# analog_project_schematic_2.net
KiCad netlist of a schematic drawn in Altium Designer
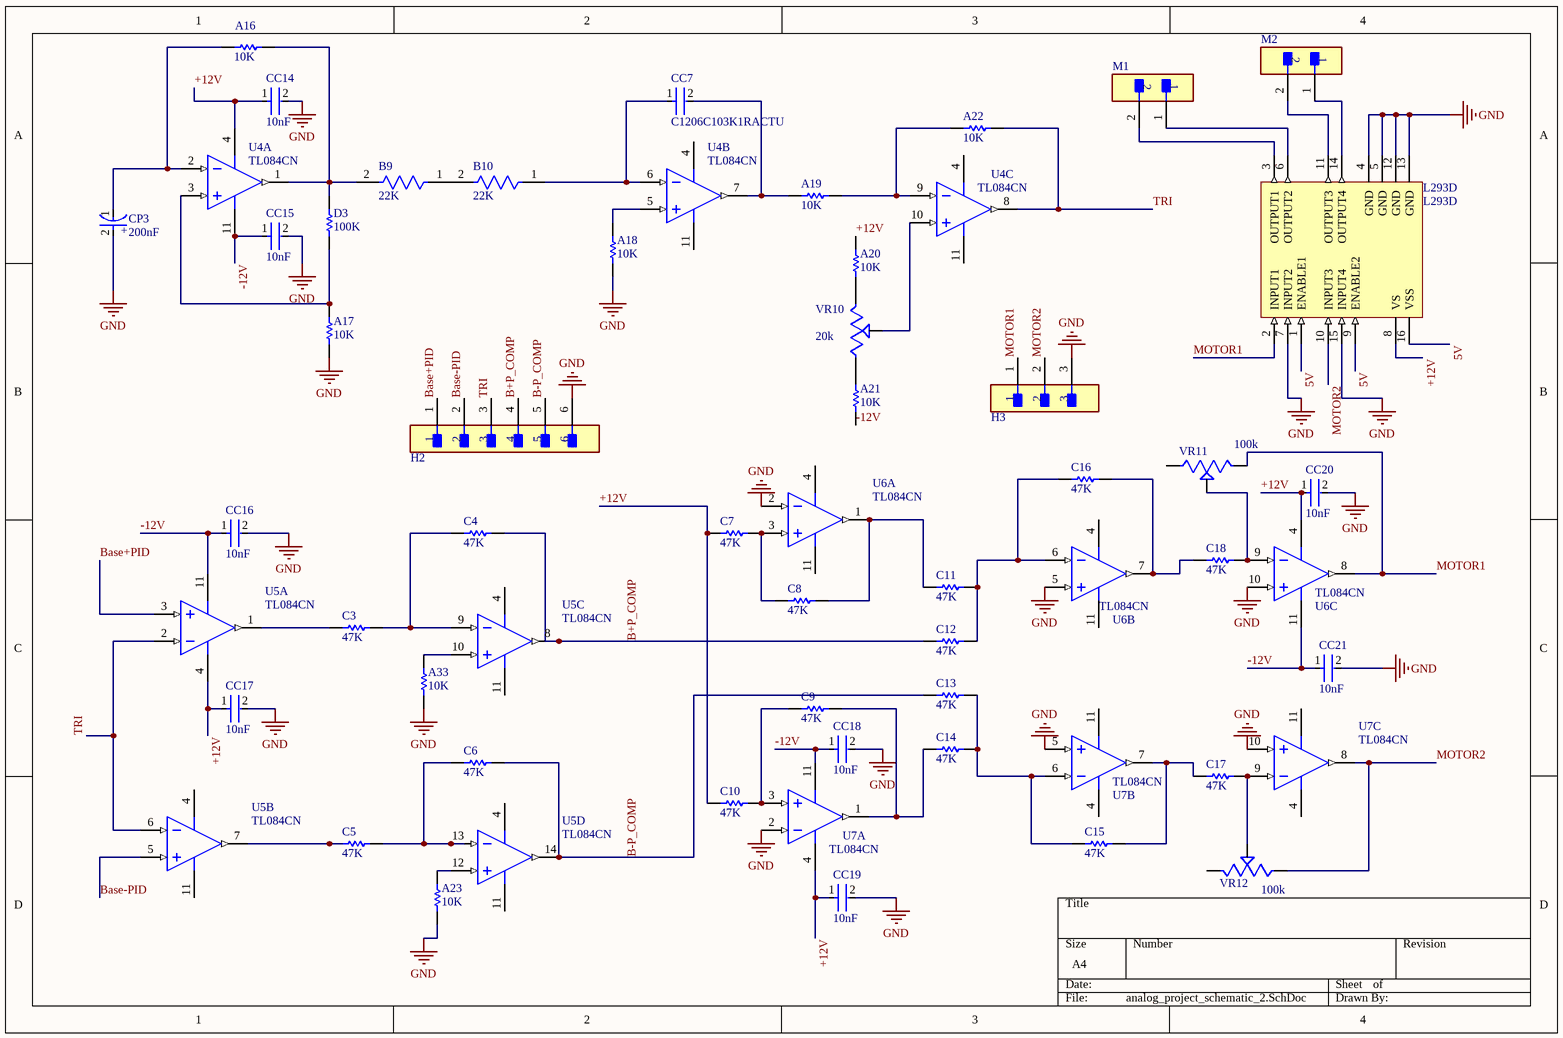
[diagram p0: analog_project_schematic_2.SchDoc]

(export (version "E")
  (design (tool "Eeschema 10.0.6"))
  (components
    (comp (ref "A16")
      (value "10K")
      (footprint "RESC3216X70X50NL05T20")
      (fields (field (name "PART NUMBER") "ERJ-8GEYJ103V") (field (name "MANUFACTURER") "Panasonic"))
      (libsource (lib "Altium Content Vault") (part "RES"))
    )
    (comp (ref "A17")
      (value "10K")
      (footprint "RESC3216X70X50NL05T20")
      (fields (field (name "PART NUMBER") "ERJ-8GEYJ103V") (field (name "MANUFACTURER") "Panasonic"))
      (libsource (lib "Altium Content Vault") (part "RES"))
    )
    (comp (ref "A18")
      (value "10K")
      (footprint "RESC3216X70X50NL05T20")
      (fields (field (name "PART NUMBER") "ERJ-8GEYJ103V") (field (name "MANUFACTURER") "Panasonic"))
      (libsource (lib "Altium Content Vault") (part "RES"))
    )
    (comp (ref "A19")
      (value "10K")
      (footprint "RESC3216X70X50NL05T20")
      (fields (field (name "PART NUMBER") "ERJ-8GEYJ103V") (field (name "MANUFACTURER") "Panasonic"))
      (libsource (lib "Altium Content Vault") (part "RES"))
    )
    (comp (ref "A20")
      (value "10K")
      (footprint "RESC3216X70X50NL05T20")
      (fields (field (name "PART NUMBER") "ERJ-8GEYJ103V") (field (name "MANUFACTURER") "Panasonic"))
      (libsource (lib "Altium Content Vault") (part "RES"))
    )
    (comp (ref "A21")
      (value "10K")
      (footprint "RESC3216X70X50NL05T20")
      (fields (field (name "PART NUMBER") "ERJ-8GEYJ103V") (field (name "MANUFACTURER") "Panasonic"))
      (libsource (lib "Altium Content Vault") (part "RES"))
    )
    (comp (ref "A22")
      (value "10K")
      (footprint "RESC3216X70X50NL05T20")
      (fields (field (name "PART NUMBER") "ERJ-8GEYJ103V") (field (name "MANUFACTURER") "Panasonic"))
      (libsource (lib "Altium Content Vault") (part "RES"))
    )
    (comp (ref "A23")
      (value "10K")
      (footprint "RESC3216X70X50NL05T20")
      (fields (field (name "PART NUMBER") "ERJ-8GEYJ103V") (field (name "MANUFACTURER") "Panasonic"))
      (libsource (lib "Altium Content Vault") (part "RES"))
    )
    (comp (ref "A33")
      (value "10K")
      (footprint "RESC3216X70X50NL05T20")
      (fields (field (name "PART NUMBER") "ERJ-8GEYJ103V") (field (name "MANUFACTURER") "Panasonic"))
      (libsource (lib "Altium Content Vault") (part "RES"))
    )
    (comp (ref "B9")
      (value "22K")
      (footprint "FP-CRCW1206-e3-IPC_A")
      (description "RES Thick Film, 22kΩ, 1%, 0.25W, 100ppm/°C, 1206")
      (fields (field (name "TOLERANCE") "1%"))
      (libsource (lib "Altium Content Vault") (part "1029c3af85768c4190bb7ad29bc67b5"))
    )
    (comp (ref "B10")
      (value "22K")
      (footprint "FP-CRCW1206-e3-IPC_A")
      (description "RES Thick Film, 22kΩ, 1%, 0.25W, 100ppm/°C, 1206")
      (fields (field (name "TOLERANCE") "1%"))
      (libsource (lib "Altium Content Vault") (part "1029c3af85768c4190bb7ad29bc67b5"))
    )
    (comp (ref "C3")
      (value "47K")
      (footprint "RESC3216X60X45LL10T20")
      (fields (field (name "PART NUMBER") "CRCW120647K0FKEA") (field (name "MANUFACTURER") "Vishay Dale"))
      (libsource (lib "Altium Content Vault") (part "RES"))
    )
    (comp (ref "C4")
      (value "47K")
      (footprint "RESC3216X60X45LL10T20")
      (fields (field (name "PART NUMBER") "CRCW120647K0FKEA") (field (name "MANUFACTURER") "Vishay Dale"))
      (libsource (lib "Altium Content Vault") (part "RES"))
    )
    (comp (ref "C5")
      (value "47K")
      (footprint "RESC3216X60X45LL10T20")
      (fields (field (name "PART NUMBER") "CRCW120647K0FKEA") (field (name "MANUFACTURER") "Vishay Dale"))
      (libsource (lib "Altium Content Vault") (part "RES"))
    )
    (comp (ref "C6")
      (value "47K")
      (footprint "RESC3216X60X45LL10T20")
      (fields (field (name "PART NUMBER") "CRCW120647K0FKEA") (field (name "MANUFACTURER") "Vishay Dale"))
      (libsource (lib "Altium Content Vault") (part "RES"))
    )
    (comp (ref "C7")
      (value "47K")
      (footprint "RESC3216X60X45LL10T20")
      (fields (field (name "PART NUMBER") "CRCW120647K0FKEA") (field (name "MANUFACTURER") "Vishay Dale"))
      (libsource (lib "Altium Content Vault") (part "RES"))
    )
    (comp (ref "C8")
      (value "47K")
      (footprint "RESC3216X60X45LL10T20")
      (fields (field (name "PART NUMBER") "CRCW120647K0FKEA") (field (name "MANUFACTURER") "Vishay Dale"))
      (libsource (lib "Altium Content Vault") (part "RES"))
    )
    (comp (ref "C9")
      (value "47K")
      (footprint "RESC3216X60X45LL10T20")
      (fields (field (name "PART NUMBER") "CRCW120647K0FKEA") (field (name "MANUFACTURER") "Vishay Dale"))
      (libsource (lib "Altium Content Vault") (part "RES"))
    )
    (comp (ref "C10")
      (value "47K")
      (footprint "RESC3216X60X45LL10T20")
      (fields (field (name "PART NUMBER") "CRCW120647K0FKEA") (field (name "MANUFACTURER") "Vishay Dale"))
      (libsource (lib "Altium Content Vault") (part "RES"))
    )
    (comp (ref "C11")
      (value "47K")
      (footprint "RESC3216X60X45LL10T20")
      (fields (field (name "PART NUMBER") "CRCW120647K0FKEA") (field (name "MANUFACTURER") "Vishay Dale"))
      (libsource (lib "Altium Content Vault") (part "RES"))
    )
    (comp (ref "C12")
      (value "47K")
      (footprint "RESC3216X60X45LL10T20")
      (fields (field (name "PART NUMBER") "CRCW120647K0FKEA") (field (name "MANUFACTURER") "Vishay Dale"))
      (libsource (lib "Altium Content Vault") (part "RES"))
    )
    (comp (ref "C13")
      (value "47K")
      (footprint "RESC3216X60X45LL10T20")
      (fields (field (name "PART NUMBER") "CRCW120647K0FKEA") (field (name "MANUFACTURER") "Vishay Dale"))
      (libsource (lib "Altium Content Vault") (part "RES"))
    )
    (comp (ref "C14")
      (value "47K")
      (footprint "RESC3216X60X45LL10T20")
      (fields (field (name "PART NUMBER") "CRCW120647K0FKEA") (field (name "MANUFACTURER") "Vishay Dale"))
      (libsource (lib "Altium Content Vault") (part "RES"))
    )
    (comp (ref "C15")
      (value "47K")
      (footprint "RESC3216X60X45LL10T20")
      (fields (field (name "PART NUMBER") "CRCW120647K0FKEA") (field (name "MANUFACTURER") "Vishay Dale"))
      (libsource (lib "Altium Content Vault") (part "RES"))
    )
    (comp (ref "C16")
      (value "47K")
      (footprint "RESC3216X60X45LL10T20")
      (fields (field (name "PART NUMBER") "CRCW120647K0FKEA") (field (name "MANUFACTURER") "Vishay Dale"))
      (libsource (lib "Altium Content Vault") (part "RES"))
    )
    (comp (ref "C17")
      (value "47K")
      (footprint "RESC3216X60X45LL10T20")
      (fields (field (name "PART NUMBER") "CRCW120647K0FKEA") (field (name "MANUFACTURER") "Vishay Dale"))
      (libsource (lib "Altium Content Vault") (part "RES"))
    )
    (comp (ref "C18")
      (value "47K")
      (footprint "RESC3216X60X45LL10T20")
      (fields (field (name "PART NUMBER") "CRCW120647K0FKEA") (field (name "MANUFACTURER") "Vishay Dale"))
      (libsource (lib "Altium Content Vault") (part "RES"))
    )
    (comp (ref "CC7")
      (value "C1206C103K1RACTU")
      (footprint "FP-C1206C-EB-MFG")
      (description "Cap Ceramic 0.01uF 100V X7R 10% SMD 1206 125°C Plastic T/R")
      (fields
        (field (name "MANUFACTURER") "KEMET")
        (field (name "OCTOPART") "https://octopart.com/c1206c103k1ractu-kemet-117927")
      )
      (libsource (lib "Altium Content Vault") (part "b4654b650e69147ec39a6b967a45e02"))
    )
    (comp (ref "CC14")
      (value "10nF")
      (footprint "FP-C1206C-EB-MFG")
      (description "Cap Ceramic 0.01uF 100V X7R 10% SMD 1206 125°C Plastic T/R")
      (fields
        (field (name "MANUFACTURER") "KEMET")
        (field (name "MANUFACTURER PART NUMBER") "C1206C103K1RACTU")
      )
      (libsource (lib "Altium Content Vault") (part "b4654b650e69147ec39a6b967a45e02"))
    )
    (comp (ref "CC15")
      (value "10nF")
      (footprint "FP-C1206C-EB-MFG")
      (description "Cap Ceramic 0.01uF 100V X7R 10% SMD 1206 125°C Plastic T/R")
      (fields
        (field (name "MANUFACTURER") "KEMET")
        (field (name "MANUFACTURER PART NUMBER") "C1206C103K1RACTU")
      )
      (libsource (lib "Altium Content Vault") (part "b4654b650e69147ec39a6b967a45e02"))
    )
    (comp (ref "CC16")
      (value "10nF")
      (footprint "FP-C1206C-EB-MFG")
      (description "Cap Ceramic 0.01uF 100V X7R 10% SMD 1206 125°C Plastic T/R")
      (fields
        (field (name "MANUFACTURER") "KEMET")
        (field (name "MANUFACTURER PART NUMBER") "C1206C103K1RACTU")
      )
      (libsource (lib "Altium Content Vault") (part "b4654b650e69147ec39a6b967a45e02"))
    )
    (comp (ref "CC17")
      (value "10nF")
      (footprint "FP-C1206C-EB-MFG")
      (description "Cap Ceramic 0.01uF 100V X7R 10% SMD 1206 125°C Plastic T/R")
      (fields
        (field (name "MANUFACTURER") "KEMET")
        (field (name "MANUFACTURER PART NUMBER") "C1206C103K1RACTU")
      )
      (libsource (lib "Altium Content Vault") (part "b4654b650e69147ec39a6b967a45e02"))
    )
    (comp (ref "CC18")
      (value "10nF")
      (footprint "FP-C1206C-EB-MFG")
      (description "Cap Ceramic 0.01uF 100V X7R 10% SMD 1206 125°C Plastic T/R")
      (fields
        (field (name "MANUFACTURER") "KEMET")
        (field (name "MANUFACTURER PART NUMBER") "C1206C103K1RACTU")
      )
      (libsource (lib "Altium Content Vault") (part "b4654b650e69147ec39a6b967a45e02"))
    )
    (comp (ref "CC19")
      (value "10nF")
      (footprint "FP-C1206C-EB-MFG")
      (description "Cap Ceramic 0.01uF 100V X7R 10% SMD 1206 125°C Plastic T/R")
      (fields
        (field (name "MANUFACTURER") "KEMET")
        (field (name "MANUFACTURER PART NUMBER") "C1206C103K1RACTU")
      )
      (libsource (lib "Altium Content Vault") (part "b4654b650e69147ec39a6b967a45e02"))
    )
    (comp (ref "CC20")
      (value "10nF")
      (footprint "FP-C1206C-EB-MFG")
      (description "Cap Ceramic 0.01uF 100V X7R 10% SMD 1206 125°C Plastic T/R")
      (fields
        (field (name "MANUFACTURER") "KEMET")
        (field (name "MANUFACTURER PART NUMBER") "C1206C103K1RACTU")
      )
      (libsource (lib "Altium Content Vault") (part "b4654b650e69147ec39a6b967a45e02"))
    )
    (comp (ref "CC21")
      (value "10nF")
      (footprint "FP-C1206C-EB-MFG")
      (description "Cap Ceramic 0.01uF 100V X7R 10% SMD 1206 125°C Plastic T/R")
      (fields
        (field (name "MANUFACTURER") "KEMET")
        (field (name "MANUFACTURER PART NUMBER") "C1206C103K1RACTU")
      )
      (libsource (lib "Altium Content Vault") (part "b4654b650e69147ec39a6b967a45e02"))
    )
    (comp (ref "CP3")
      (value "200nF")
      (footprint "FP-EEU-FR1H101B-MFG")
      (description "CAP ALUM 100UF 20% 50V RADIAL")
      (fields (field (name "TOLERANCE") "20%"))
      (libsource (lib "Altium Content Vault") (part "cf48714ba7e38822c1575c7ec0b6d1f"))
    )
    (comp (ref "D3")
      (value "100K")
      (footprint "RESC3216X60X45NL10T20")
      (fields (field (name "PART NUMBER") "CRCW1206100KFKEA") (field (name "MANUFACTURER") "Vishay Dale"))
      (libsource (lib "Altium Content Vault") (part "RES"))
    )
    (comp (ref "H2")
      (value "PEC06SBBN")
      (footprint "FP-PEC06SBBN-MFG")
      (description "CONN HEADER R/A 6POS 2.54MM")
      (libsource (lib "Altium Content Vault") (part "f2cb566baf1c37ab5a3b8e90bbeafd6"))
    )
    (comp (ref "H3")
      (value "NRPN031PAEN-RC")
      (footprint "FP-NRPN031PAEN-RC-MFG")
      (description "Connector Header Through Hole 3 position 0.079\" (2.00mm)")
      (fields (field (name "OCTOPART") "https://octopart.com/nrpn031paen-rc-sullins-12817732"))
      (libsource (lib "Altium Content Vault") (part "0d3f023dd272f625e17a2be33dea85f"))
    )
    (comp (ref "L293D")
      (value "L293D")
      (footprint "STM-L293D-16")
      (description "Push-Pull Four Channel Driver with Diode, 4.5 to 36 V, -40 to 150 degC, 16-Pin PDIP, RoHS, Tube")
      (fields (field (name "MANUFACTURER") "STMicroelectronics"))
      (libsource (lib "Altium Content Vault") (part "STM-L293D-16"))
    )
    (comp (ref "M1")
      (value "B2B-XH-A(LF)(SN)")
      (footprint "FP-B2B-XH-A_LF_SN-MFG")
      (description "CONN HEADER VERT 2POS 2.5MM")
      (libsource (lib "Altium Content Vault") (part "3bc925449376181038e59eaffc5286c"))
    )
    (comp (ref "M2")
      (value "B2B-XH-A(LF)(SN)")
      (footprint "FP-B2B-XH-A_LF_SN-MFG")
      (description "CONN HEADER VERT 2POS 2.5MM")
      (libsource (lib "Altium Content Vault") (part "3bc925449376181038e59eaffc5286c"))
    )
    (comp (ref "U4")
      (value "TL084CN")
      (footprint "N0014A")
      (description "JFET-Input Operational Amplifier, 7 to 36 V, 0 to 70 degC, 14-pin DIP (N14), Pb-Free (RoHS)")
      (fields (field (name "MANUFACTURER") "Texas Instruments"))
      (libsource (lib "Altium Content Vault") (part "TI-TLXX4X_MC3403-X14"))
    )
    (comp (ref "U5")
      (value "TL084CN")
      (footprint "N0014A")
      (description "JFET-Input Operational Amplifier, 7 to 36 V, 0 to 70 degC, 14-pin DIP (N14), Pb-Free (RoHS)")
      (fields (field (name "MANUFACTURER") "Texas Instruments"))
      (libsource (lib "Altium Content Vault") (part "TI-TLXX4X_MC3403-X14"))
    )
    (comp (ref "U6")
      (value "TL084CN")
      (footprint "N0014A")
      (description "JFET-Input Operational Amplifier, 7 to 36 V, 0 to 70 degC, 14-pin DIP (N14), Pb-Free (RoHS)")
      (fields (field (name "MANUFACTURER") "Texas Instruments"))
      (libsource (lib "Altium Content Vault") (part "TI-TLXX4X_MC3403-X14"))
    )
    (comp (ref "U7")
      (value "TL084CN")
      (footprint "N0014A")
      (description "JFET-Input Operational Amplifier, 7 to 36 V, 0 to 70 degC, 14-pin DIP (N14), Pb-Free (RoHS)")
      (fields (field (name "MANUFACTURER") "Texas Instruments"))
      (libsource (lib "Altium Content Vault") (part "TI-TLXX4X_MC3403-X14"))
    )
    (comp (ref "VR10")
      (value "20k")
      (footprint "TRIM_3296Y-1-104")
      (fields (field (name "MP") "3296Y-1-104"))
      (libsource (lib "3296Y-1-104") (part "3296Y-1-104"))
    )
    (comp (ref "VR11")
      (value "100k")
      (footprint "TRIM_3296Y-1-104")
      (fields (field (name "MP") "3296Y-1-104"))
      (libsource (lib "3296Y-1-104") (part "3296Y-1-104"))
    )
    (comp (ref "VR12")
      (value "100k")
      (footprint "TRIM_3296Y-1-104")
      (fields (field (name "MP") "3296Y-1-104"))
      (libsource (lib "3296Y-1-104") (part "3296Y-1-104"))
    )
  )
  (nets
    (net (code "1") (name "/+12V") (class "Default")
      (node (ref "A20") (pin "2") (pinfunction "2_2") (pintype "passive"))
      (node (ref "C10") (pin "1") (pinfunction "1_1") (pintype "passive"))
      (node (ref "C7") (pin "1") (pinfunction "1_1") (pintype "passive"))
      (node (ref "CC14") (pin "1") (pinfunction "1_1") (pintype "passive"))
      (node (ref "CC17") (pin "1") (pinfunction "1_1") (pintype "passive"))
      (node (ref "CC19") (pin "1") (pinfunction "1_1") (pintype "passive"))
      (node (ref "CC20") (pin "1") (pinfunction "1_1") (pintype "passive"))
      (node (ref "L293D") (pin "8") (pinfunction "VS_8") (pintype "power_in"))
      (node (ref "U4") (pin "4") (pinfunction "VCC+_4") (pintype "power_in"))
      (node (ref "U5") (pin "4") (pinfunction "VCC+_4") (pintype "power_in"))
      (node (ref "U6") (pin "4") (pinfunction "VCC+_4") (pintype "power_in"))
      (node (ref "U7") (pin "4") (pinfunction "VCC+_4") (pintype "power_in"))
    )
    (net (code "2") (name "/-12V") (class "Default")
      (node (ref "A21") (pin "1") (pinfunction "1_1") (pintype "passive"))
      (node (ref "CC15") (pin "1") (pinfunction "1_1") (pintype "passive"))
      (node (ref "CC16") (pin "1") (pinfunction "1_1") (pintype "passive"))
      (node (ref "CC18") (pin "1") (pinfunction "1_1") (pintype "passive"))
      (node (ref "CC21") (pin "1") (pinfunction "1_1") (pintype "passive"))
      (node (ref "U4") (pin "11") (pinfunction "VCC-_11") (pintype "power_in"))
      (node (ref "U5") (pin "11") (pinfunction "VCC-_11") (pintype "power_in"))
      (node (ref "U6") (pin "11") (pinfunction "VCC-_11") (pintype "power_in"))
      (node (ref "U7") (pin "11") (pinfunction "VCC-_11") (pintype "power_in"))
    )
    (net (code "3") (name "/5V") (class "Default")
      (node (ref "L293D") (pin "1") (pinfunction "ENABLE1_1") (pintype "input"))
      (node (ref "L293D") (pin "16") (pinfunction "VSS_16") (pintype "power_in"))
      (node (ref "L293D") (pin "9") (pinfunction "ENABLE2_9") (pintype "input"))
    )
    (net (code "4") (name "/B+P_COMP") (class "Default")
      (node (ref "C12") (pin "1") (pinfunction "1_1") (pintype "passive"))
      (node (ref "C4") (pin "2") (pinfunction "2_2") (pintype "passive"))
      (node (ref "H2") (pin "4") (pinfunction "4_4") (pintype "passive"))
      (node (ref "U5") (pin "8") (pinfunction "OUT3_8") (pintype "output"))
    )
    (net (code "5") (name "/B-P_COMP") (class "Default")
      (node (ref "C13") (pin "1") (pinfunction "1_1") (pintype "passive"))
      (node (ref "C6") (pin "2") (pinfunction "2_2") (pintype "passive"))
      (node (ref "H2") (pin "5") (pinfunction "5_5") (pintype "passive"))
      (node (ref "U5") (pin "14") (pinfunction "OUT4_14") (pintype "output"))
    )
    (net (code "6") (name "/Base+PID") (class "Default")
      (node (ref "H2") (pin "1") (pinfunction "1_1") (pintype "passive"))
      (node (ref "U5") (pin "3") (pinfunction "IN1+_3") (pintype "input"))
    )
    (net (code "7") (name "/Base-PID") (class "Default")
      (node (ref "H2") (pin "2") (pinfunction "2_2") (pintype "passive"))
      (node (ref "U5") (pin "5") (pinfunction "IN2+_5") (pintype "input"))
    )
    (net (code "8") (name "/MOTOR1") (class "Default")
      (node (ref "H3") (pin "1") (pinfunction "1_1") (pintype "passive"))
      (node (ref "L293D") (pin "2") (pinfunction "INPUT1_2") (pintype "input"))
      (node (ref "U6") (pin "8") (pinfunction "OUT3_8") (pintype "output"))
      (node (ref "VR11") (pin "1") (pinfunction "CCW_1") (pintype "passive"))
    )
    (net (code "9") (name "/MOTOR2") (class "Default")
      (node (ref "H3") (pin "2") (pinfunction "2_2") (pintype "passive"))
      (node (ref "L293D") (pin "10") (pinfunction "INPUT3_10") (pintype "input"))
      (node (ref "U7") (pin "8") (pinfunction "OUT3_8") (pintype "output"))
      (node (ref "VR12") (pin "1") (pinfunction "CCW_1") (pintype "passive"))
    )
    (net (code "10") (name "/TRI") (class "Default")
      (node (ref "A22") (pin "2") (pinfunction "2_2") (pintype "passive"))
      (node (ref "H2") (pin "3") (pinfunction "3_3") (pintype "passive"))
      (node (ref "U4") (pin "8") (pinfunction "OUT3_8") (pintype "output"))
      (node (ref "U5") (pin "2") (pinfunction "IN1-_2") (pintype "input"))
      (node (ref "U5") (pin "6") (pinfunction "IN2-_6") (pintype "input"))
    )
    (net (code "11") (name "GND") (class "Default")
      (node (ref "A17") (pin "1") (pinfunction "1_1") (pintype "passive"))
      (node (ref "A18") (pin "1") (pinfunction "1_1") (pintype "passive"))
      (node (ref "A23") (pin "1") (pinfunction "1_1") (pintype "passive"))
      (node (ref "A33") (pin "1") (pinfunction "1_1") (pintype "passive"))
      (node (ref "CC14") (pin "2") (pinfunction "2_2") (pintype "passive"))
      (node (ref "CC15") (pin "2") (pinfunction "2_2") (pintype "passive"))
      (node (ref "CC16") (pin "2") (pinfunction "2_2") (pintype "passive"))
      (node (ref "CC17") (pin "2") (pinfunction "2_2") (pintype "passive"))
      (node (ref "CC18") (pin "2") (pinfunction "2_2") (pintype "passive"))
      (node (ref "CC19") (pin "2") (pinfunction "2_2") (pintype "passive"))
      (node (ref "CC20") (pin "2") (pinfunction "2_2") (pintype "passive"))
      (node (ref "CC21") (pin "2") (pinfunction "2_2") (pintype "passive"))
      (node (ref "CP3") (pin "2") (pinfunction "A_2") (pintype "passive"))
      (node (ref "H2") (pin "6") (pinfunction "6_6") (pintype "passive"))
      (node (ref "H3") (pin "3") (pinfunction "3_3") (pintype "passive"))
      (node (ref "L293D") (pin "12") (pinfunction "GND_12") (pintype "power_in"))
      (node (ref "L293D") (pin "13") (pinfunction "GND_13") (pintype "power_in"))
      (node (ref "L293D") (pin "15") (pinfunction "INPUT4_15") (pintype "input"))
      (node (ref "L293D") (pin "4") (pinfunction "GND_4") (pintype "power_in"))
      (node (ref "L293D") (pin "5") (pinfunction "GND_5") (pintype "power_in"))
      (node (ref "L293D") (pin "7") (pinfunction "INPUT2_7") (pintype "input"))
      (node (ref "U6") (pin "10") (pinfunction "IN3+_10") (pintype "input"))
      (node (ref "U6") (pin "2") (pinfunction "IN1-_2") (pintype "input"))
      (node (ref "U6") (pin "5") (pinfunction "IN2+_5") (pintype "input"))
      (node (ref "U7") (pin "10") (pinfunction "IN3+_10") (pintype "input"))
      (node (ref "U7") (pin "2") (pinfunction "IN1-_2") (pintype "input"))
      (node (ref "U7") (pin "5") (pinfunction "IN2+_5") (pintype "input"))
    )
    (net (code "12") (name "Net-(B10-Pad2)") (class "Default")
      (node (ref "B10") (pin "2") (pinfunction "2_2") (pintype "passive"))
      (node (ref "B9") (pin "1") (pinfunction "1_1") (pintype "passive"))
    )
    (net (code "13") (name "Net-(CP3-C)") (class "Default")
      (node (ref "A16") (pin "1") (pinfunction "1_1") (pintype "passive"))
      (node (ref "CP3") (pin "1") (pinfunction "C_1") (pintype "passive"))
      (node (ref "U4") (pin "2") (pinfunction "IN1-_2") (pintype "input"))
    )
    (net (code "14") (name "Net-(L293D-OUTPUT1)") (class "Default")
      (node (ref "L293D") (pin "3") (pinfunction "OUTPUT1_3") (pintype "output"))
      (node (ref "M1") (pin "2") (pinfunction "2_2") (pintype "passive"))
    )
    (net (code "15") (name "Net-(L293D-OUTPUT2)") (class "Default")
      (node (ref "L293D") (pin "6") (pinfunction "OUTPUT2_6") (pintype "output"))
      (node (ref "M1") (pin "1") (pinfunction "1_1") (pintype "passive"))
    )
    (net (code "16") (name "Net-(L293D-OUTPUT3)") (class "Default")
      (node (ref "L293D") (pin "11") (pinfunction "OUTPUT3_11") (pintype "output"))
      (node (ref "M2") (pin "2") (pinfunction "2_2") (pintype "passive"))
    )
    (net (code "17") (name "Net-(L293D-OUTPUT4)") (class "Default")
      (node (ref "L293D") (pin "14") (pinfunction "OUTPUT4_14") (pintype "output"))
      (node (ref "M2") (pin "1") (pinfunction "1_1") (pintype "passive"))
    )
    (net (code "18") (name "Net-(U4A-IN1+)") (class "Default")
      (node (ref "A17") (pin "2") (pinfunction "2_2") (pintype "passive"))
      (node (ref "D3") (pin "1") (pinfunction "1_1") (pintype "passive"))
      (node (ref "U4") (pin "3") (pinfunction "IN1+_3") (pintype "input"))
    )
    (net (code "19") (name "Net-(U4A-OUT1)") (class "Default")
      (node (ref "A16") (pin "2") (pinfunction "2_2") (pintype "passive"))
      (node (ref "B9") (pin "2") (pinfunction "2_2") (pintype "passive"))
      (node (ref "D3") (pin "2") (pinfunction "2_2") (pintype "passive"))
      (node (ref "U4") (pin "1") (pinfunction "OUT1_1") (pintype "output"))
    )
    (net (code "20") (name "Net-(U4B-IN2+)") (class "Default")
      (node (ref "A18") (pin "2") (pinfunction "2_2") (pintype "passive"))
      (node (ref "U4") (pin "5") (pinfunction "IN2+_5") (pintype "input"))
    )
    (net (code "21") (name "Net-(U4B-IN2-)") (class "Default")
      (node (ref "B10") (pin "1") (pinfunction "1_1") (pintype "passive"))
      (node (ref "CC7") (pin "1") (pinfunction "1_1") (pintype "passive"))
      (node (ref "U4") (pin "6") (pinfunction "IN2-_6") (pintype "input"))
    )
    (net (code "22") (name "Net-(U4B-OUT2)") (class "Default")
      (node (ref "A19") (pin "1") (pinfunction "1_1") (pintype "passive"))
      (node (ref "CC7") (pin "2") (pinfunction "2_2") (pintype "passive"))
      (node (ref "U4") (pin "7") (pinfunction "OUT2_7") (pintype "output"))
    )
    (net (code "23") (name "Net-(U4C-IN3+)") (class "Default")
      (node (ref "U4") (pin "10") (pinfunction "IN3+_10") (pintype "input"))
      (node (ref "VR10") (pin "2") (pinfunction "WIPER_2") (pintype "passive"))
    )
    (net (code "24") (name "Net-(U4C-IN3-)") (class "Default")
      (node (ref "A19") (pin "2") (pinfunction "2_2") (pintype "passive"))
      (node (ref "A22") (pin "1") (pinfunction "1_1") (pintype "passive"))
      (node (ref "U4") (pin "9") (pinfunction "IN3-_9") (pintype "input"))
    )
    (net (code "25") (name "Net-(U5A-OUT1)") (class "Default")
      (node (ref "C3") (pin "1") (pinfunction "1_1") (pintype "passive"))
      (node (ref "U5") (pin "1") (pinfunction "OUT1_1") (pintype "output"))
    )
    (net (code "26") (name "Net-(U5B-OUT2)") (class "Default")
      (node (ref "C5") (pin "1") (pinfunction "1_1") (pintype "passive"))
      (node (ref "U5") (pin "7") (pinfunction "OUT2_7") (pintype "output"))
    )
    (net (code "27") (name "Net-(U5C-IN3+)") (class "Default")
      (node (ref "A33") (pin "2") (pinfunction "2_2") (pintype "passive"))
      (node (ref "U5") (pin "10") (pinfunction "IN3+_10") (pintype "input"))
    )
    (net (code "28") (name "Net-(U5C-IN3-)") (class "Default")
      (node (ref "C3") (pin "2") (pinfunction "2_2") (pintype "passive"))
      (node (ref "C4") (pin "1") (pinfunction "1_1") (pintype "passive"))
      (node (ref "U5") (pin "9") (pinfunction "IN3-_9") (pintype "input"))
    )
    (net (code "29") (name "Net-(U5D-IN4+)") (class "Default")
      (node (ref "A23") (pin "2") (pinfunction "2_2") (pintype "passive"))
      (node (ref "U5") (pin "12") (pinfunction "IN4+_12") (pintype "input"))
    )
    (net (code "30") (name "Net-(U5D-IN4-)") (class "Default")
      (node (ref "C5") (pin "2") (pinfunction "2_2") (pintype "passive"))
      (node (ref "C6") (pin "1") (pinfunction "1_1") (pintype "passive"))
      (node (ref "U5") (pin "13") (pinfunction "IN4-_13") (pintype "input"))
    )
    (net (code "31") (name "Net-(U6A-IN1+)") (class "Default")
      (node (ref "C7") (pin "2") (pinfunction "2_2") (pintype "passive"))
      (node (ref "C8") (pin "1") (pinfunction "1_1") (pintype "passive"))
      (node (ref "U6") (pin "3") (pinfunction "IN1+_3") (pintype "input"))
    )
    (net (code "32") (name "Net-(U6A-OUT1)") (class "Default")
      (node (ref "C11") (pin "1") (pinfunction "1_1") (pintype "passive"))
      (node (ref "C8") (pin "2") (pinfunction "2_2") (pintype "passive"))
      (node (ref "U6") (pin "1") (pinfunction "OUT1_1") (pintype "output"))
    )
    (net (code "33") (name "Net-(U6B-IN2-)") (class "Default")
      (node (ref "C11") (pin "2") (pinfunction "2_2") (pintype "passive"))
      (node (ref "C12") (pin "2") (pinfunction "2_2") (pintype "passive"))
      (node (ref "C16") (pin "1") (pinfunction "1_1") (pintype "passive"))
      (node (ref "U6") (pin "6") (pinfunction "IN2-_6") (pintype "input"))
    )
    (net (code "34") (name "Net-(U6B-OUT2)") (class "Default")
      (node (ref "C16") (pin "2") (pinfunction "2_2") (pintype "passive"))
      (node (ref "C18") (pin "1") (pinfunction "1_1") (pintype "passive"))
      (node (ref "U6") (pin "7") (pinfunction "OUT2_7") (pintype "output"))
    )
    (net (code "35") (name "Net-(U6C-IN3-)") (class "Default")
      (node (ref "C18") (pin "2") (pinfunction "2_2") (pintype "passive"))
      (node (ref "U6") (pin "9") (pinfunction "IN3-_9") (pintype "input"))
      (node (ref "VR11") (pin "2") (pinfunction "WIPER_2") (pintype "passive"))
    )
    (net (code "36") (name "Net-(U7A-IN1+)") (class "Default")
      (node (ref "C10") (pin "2") (pinfunction "2_2") (pintype "passive"))
      (node (ref "C9") (pin "1") (pinfunction "1_1") (pintype "passive"))
      (node (ref "U7") (pin "3") (pinfunction "IN1+_3") (pintype "input"))
    )
    (net (code "37") (name "Net-(U7A-OUT1)") (class "Default")
      (node (ref "C14") (pin "1") (pinfunction "1_1") (pintype "passive"))
      (node (ref "C9") (pin "2") (pinfunction "2_2") (pintype "passive"))
      (node (ref "U7") (pin "1") (pinfunction "OUT1_1") (pintype "output"))
    )
    (net (code "38") (name "Net-(U7B-IN2-)") (class "Default")
      (node (ref "C13") (pin "2") (pinfunction "2_2") (pintype "passive"))
      (node (ref "C14") (pin "2") (pinfunction "2_2") (pintype "passive"))
      (node (ref "C15") (pin "1") (pinfunction "1_1") (pintype "passive"))
      (node (ref "U7") (pin "6") (pinfunction "IN2-_6") (pintype "input"))
    )
    (net (code "39") (name "Net-(U7B-OUT2)") (class "Default")
      (node (ref "C15") (pin "2") (pinfunction "2_2") (pintype "passive"))
      (node (ref "C17") (pin "1") (pinfunction "1_1") (pintype "passive"))
      (node (ref "U7") (pin "7") (pinfunction "OUT2_7") (pintype "output"))
    )
    (net (code "40") (name "Net-(U7C-IN3-)") (class "Default")
      (node (ref "C17") (pin "2") (pinfunction "2_2") (pintype "passive"))
      (node (ref "U7") (pin "9") (pinfunction "IN3-_9") (pintype "input"))
      (node (ref "VR12") (pin "2") (pinfunction "WIPER_2") (pintype "passive"))
    )
    (net (code "41") (name "Net-(VR10-CCW)") (class "Default")
      (node (ref "A20") (pin "1") (pinfunction "1_1") (pintype "passive"))
      (node (ref "VR10") (pin "1") (pinfunction "CCW_1") (pintype "passive"))
    )
    (net (code "42") (name "Net-(VR10-CW)") (class "Default")
      (node (ref "A21") (pin "2") (pinfunction "2_2") (pintype "passive"))
      (node (ref "VR10") (pin "3") (pinfunction "CW_3") (pintype "passive"))
    )
    (net (code "43") (name "unconnected-(U4B-VCC+-Pad4)") (class "Default")
      (node (ref "U4") (pin "4") (pinfunction "VCC+_4") (pintype "power_in"))
    )
    (net (code "44") (name "unconnected-(U4B-VCC--Pad11)") (class "Default")
      (node (ref "U4") (pin "11") (pinfunction "VCC-_11") (pintype "power_in"))
    )
    (net (code "45") (name "unconnected-(U4C-VCC+-Pad4)") (class "Default")
      (node (ref "U4") (pin "4") (pinfunction "VCC+_4") (pintype "power_in"))
    )
    (net (code "46") (name "unconnected-(U4C-VCC--Pad11)") (class "Default")
      (node (ref "U4") (pin "11") (pinfunction "VCC-_11") (pintype "power_in"))
    )
    (net (code "47") (name "unconnected-(U5B-VCC+-Pad4)") (class "Default")
      (node (ref "U5") (pin "4") (pinfunction "VCC+_4") (pintype "power_in"))
    )
    (net (code "48") (name "unconnected-(U5B-VCC--Pad11)") (class "Default")
      (node (ref "U5") (pin "11") (pinfunction "VCC-_11") (pintype "power_in"))
    )
    (net (code "49") (name "unconnected-(U5C-VCC+-Pad4)") (class "Default")
      (node (ref "U5") (pin "4") (pinfunction "VCC+_4") (pintype "power_in"))
    )
    (net (code "50") (name "unconnected-(U5C-VCC--Pad11)") (class "Default")
      (node (ref "U5") (pin "11") (pinfunction "VCC-_11") (pintype "power_in"))
    )
    (net (code "51") (name "unconnected-(U5D-VCC+-Pad4)") (class "Default")
      (node (ref "U5") (pin "4") (pinfunction "VCC+_4") (pintype "power_in"))
    )
    (net (code "52") (name "unconnected-(U5D-VCC--Pad11)") (class "Default")
      (node (ref "U5") (pin "11") (pinfunction "VCC-_11") (pintype "power_in"))
    )
    (net (code "53") (name "unconnected-(U6A-VCC+-Pad4)") (class "Default")
      (node (ref "U6") (pin "4") (pinfunction "VCC+_4") (pintype "power_in"))
    )
    (net (code "54") (name "unconnected-(U6A-VCC--Pad11)") (class "Default")
      (node (ref "U6") (pin "11") (pinfunction "VCC-_11") (pintype "power_in"))
    )
    (net (code "55") (name "unconnected-(U6B-VCC+-Pad4)") (class "Default")
      (node (ref "U6") (pin "4") (pinfunction "VCC+_4") (pintype "power_in"))
    )
    (net (code "56") (name "unconnected-(U6B-VCC--Pad11)") (class "Default")
      (node (ref "U6") (pin "11") (pinfunction "VCC-_11") (pintype "power_in"))
    )
    (net (code "57") (name "unconnected-(U7B-VCC+-Pad4)") (class "Default")
      (node (ref "U7") (pin "4") (pinfunction "VCC+_4") (pintype "power_in"))
    )
    (net (code "58") (name "unconnected-(U7B-VCC--Pad11)") (class "Default")
      (node (ref "U7") (pin "11") (pinfunction "VCC-_11") (pintype "power_in"))
    )
    (net (code "59") (name "unconnected-(U7C-VCC+-Pad4)") (class "Default")
      (node (ref "U7") (pin "4") (pinfunction "VCC+_4") (pintype "power_in"))
    )
    (net (code "60") (name "unconnected-(U7C-VCC--Pad11)") (class "Default")
      (node (ref "U7") (pin "11") (pinfunction "VCC-_11") (pintype "power_in"))
    )
    (net (code "61") (name "unconnected-(VR11-CW-Pad3)") (class "Default")
      (node (ref "VR11") (pin "3") (pinfunction "CW_3") (pintype "passive"))
    )
    (net (code "62") (name "unconnected-(VR12-CW-Pad3)") (class "Default")
      (node (ref "VR12") (pin "3") (pinfunction "CW_3") (pintype "passive"))
    )
  )
)
